# 5V_buck.net
KiCad netlist of a schematic drawn in Altium Designer
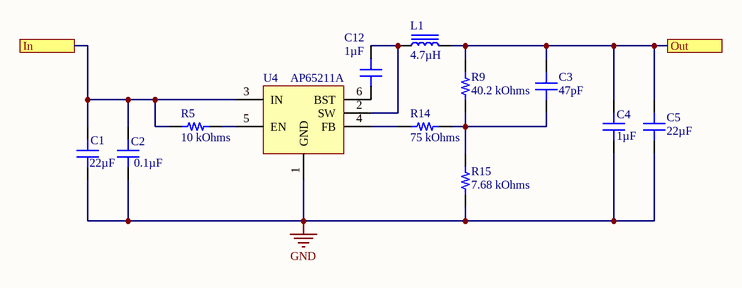
[diagram p0: 5V_buck.SchDoc]

(export (version "E")
  (design (tool "Eeschema 10.0.6"))
  (components
    (comp (ref "C1")
      (value "22µF")
      (footprint "CAP 0805_2012")
      (description "CAP CER 10UF 25V X7S 0805")
      (fields
        (field (name "PART NUMBER") "C2012X7S1E106K125AC")
        (field (name "MANUFACTURER") "TDK Corporation")
      )
      (libsource (lib "Celestial Altium Library - altium_library") (part "Capacitor"))
    )
    (comp (ref "C2")
      (value "0.1µF")
      (footprint "CAP 0603_1608")
      (description "CAP CER 0.1UF 100V 0603 EPOXY")
      (fields
        (field (name "PART NUMBER") "GCG188R92A104KA03D")
        (field (name "MANUFACTURER") "Murata Electronics")
      )
      (libsource (lib "Celestial Altium Library - altium_library") (part "Capacitor"))
    )
    (comp (ref "C3")
      (value "47pF")
      (footprint "CAP 0603_1608")
      (description "CAP CER 47PF 100V NP0 0603")
      (fields
        (field (name "PART NUMBER") "C1608NP02A470J080AA")
        (field (name "MANUFACTURER") "TDK Corporation")
      )
      (libsource (lib "Celestial Altium Library - altium_library") (part "Capacitor"))
    )
    (comp (ref "C4")
      (value "1µF")
      (footprint "CAP 0603_1608")
      (description "CAP CER 1UF 25V X7R 0603")
      (fields
        (field (name "PART NUMBER") "GCJ188R71E105KA01D")
        (field (name "MANUFACTURER") "Murata Electronics")
      )
      (libsource (lib "Celestial Altium Library - altium_library") (part "Capacitor"))
    )
    (comp (ref "C5")
      (value "22µF")
      (footprint "CAP 0805_2012")
      (description "CAP CER 22UF 16V X5R 0805")
      (fields
        (field (name "PART NUMBER") "CL21A226MOQNNNE")
        (field (name "MANUFACTURER") "Samsung Electro-Mechanics")
      )
      (libsource (lib "Celestial Altium Library - altium_library") (part "Capacitor"))
    )
    (comp (ref "C12")
      (value "1µF")
      (footprint "CAP 0603_1608")
      (description "CAP CER 1UF 25V X7R 0603")
      (fields
        (field (name "PART NUMBER") "GCJ188R71E105KA01D")
        (field (name "MANUFACTURER") "Murata Electronics")
      )
      (libsource (lib "Celestial Altium Library - altium_library") (part "Capacitor"))
    )
    (comp (ref "L1")
      (value "4.7µH")
      (footprint "IND 1008_2520")
      (description "FIXED IND 4.7UH 1A 110 MOHM SMD")
      (fields (field (name "PART NUMBER") "MLP2520S4R7ST0S1") (field (name "MANUFACTURER") "TDK Corporation"))
      (libsource (lib "Celestial Altium Library - altium_library") (part "Inductor"))
    )
    (comp (ref "R5")
      (value "10 kOhms")
      (footprint "RES 0603_1608")
      (description "RES 10K OHM 0.1% 1/16W 0603")
      (fields
        (field (name "PART NUMBER") "RNCS0603BKE10K0")
        (field (name "MANUFACTURER") "Stackpole Electronics Inc")
      )
      (libsource (lib "Celestial Altium Library - altium_library") (part "Resistor"))
    )
    (comp (ref "R9")
      (value "40.2 kOhms")
      (footprint "RES 0603_1608")
      (description "RES SMD 40.2KOHM 0.5% 1/10W 0603")
      (fields (field (name "PART NUMBER") "RT0603DRD0740K2L") (field (name "MANUFACTURER") "Yageo"))
      (libsource (lib "Celestial Altium Library - altium_library") (part "Resistor"))
    )
    (comp (ref "R14")
      (value "75 kOhms")
      (footprint "RES 0603_1608")
      (description "RES SMD 75K OHM 5% 1/10W 0603")
      (fields (field (name "PART NUMBER") "CR0603-JW-753ELF") (field (name "MANUFACTURER") "Bourns Inc."))
      (libsource (lib "Celestial Altium Library - altium_library") (part "Resistor"))
    )
    (comp (ref "R15")
      (value "7.68 kOhms")
      (footprint "RES 0603_1608")
      (description "RES 7.68K OHM 1% 1/10W 0603")
      (fields
        (field (name "PART NUMBER") "RMCF0603FT7K68")
        (field (name "MANUFACTURER") "Stackpole Electronics Inc")
      )
      (libsource (lib "Celestial Altium Library - altium_library") (part "Resistor"))
    )
    (comp (ref "U4")
      (value "AP65211A")
      (footprint "TSOT-26-6")
      (description "ADJ step down Buck")
      (libsource (lib "IC") (part "AP65211A"))
    )
  )
  (nets
    (net (code "1") (name "/In") (class "Default")
      (node (ref "C1") (pin "2") (pinfunction "2_2") (pintype "passive"))
      (node (ref "C2") (pin "1") (pinfunction "1_1") (pintype "passive"))
      (node (ref "R5") (pin "2") (pinfunction "2_2") (pintype "passive"))
      (node (ref "U4") (pin "3") (pinfunction "IN_3") (pintype "passive"))
    )
    (net (code "2") (name "/Out") (class "Default")
      (node (ref "C3") (pin "2") (pinfunction "2_2") (pintype "passive"))
      (node (ref "C4") (pin "2") (pinfunction "2_2") (pintype "passive"))
      (node (ref "C5") (pin "2") (pinfunction "2_2") (pintype "passive"))
      (node (ref "L1") (pin "2") (pinfunction "2_2") (pintype "passive"))
      (node (ref "R9") (pin "2") (pinfunction "2_2") (pintype "passive"))
    )
    (net (code "3") (name "GND") (class "Default")
      (node (ref "C1") (pin "1") (pinfunction "1_1") (pintype "passive"))
      (node (ref "C2") (pin "2") (pinfunction "2_2") (pintype "passive"))
      (node (ref "C4") (pin "1") (pinfunction "1_1") (pintype "passive"))
      (node (ref "C5") (pin "1") (pinfunction "1_1") (pintype "passive"))
      (node (ref "R15") (pin "1") (pinfunction "1_1") (pintype "passive"))
      (node (ref "U4") (pin "1") (pinfunction "GND_1") (pintype "passive"))
    )
    (net (code "4") (name "Net-(C3-Pad1)") (class "Default")
      (node (ref "C3") (pin "1") (pinfunction "1_1") (pintype "passive"))
      (node (ref "R14") (pin "2") (pinfunction "2_2") (pintype "passive"))
      (node (ref "R15") (pin "2") (pinfunction "2_2") (pintype "passive"))
      (node (ref "R9") (pin "1") (pinfunction "1_1") (pintype "passive"))
    )
    (net (code "5") (name "Net-(U4-BST)") (class "Default")
      (node (ref "C12") (pin "2") (pinfunction "2_2") (pintype "passive"))
      (node (ref "U4") (pin "6") (pinfunction "BST_6") (pintype "passive"))
    )
    (net (code "6") (name "Net-(U4-EN)") (class "Default")
      (node (ref "R5") (pin "1") (pinfunction "1_1") (pintype "passive"))
      (node (ref "U4") (pin "5") (pinfunction "EN_5") (pintype "passive"))
    )
    (net (code "7") (name "Net-(U4-FB)") (class "Default")
      (node (ref "R14") (pin "1") (pinfunction "1_1") (pintype "passive"))
      (node (ref "U4") (pin "4") (pinfunction "FB_4") (pintype "passive"))
    )
    (net (code "8") (name "Net-(U4-SW)") (class "Default")
      (node (ref "C12") (pin "1") (pinfunction "1_1") (pintype "passive"))
      (node (ref "L1") (pin "1") (pinfunction "1_1") (pintype "passive"))
      (node (ref "U4") (pin "2") (pinfunction "SW_2") (pintype "passive"))
    )
  )
)
